# EFR32_IO.net
KiCad netlist of a schematic drawn in Altium Designer
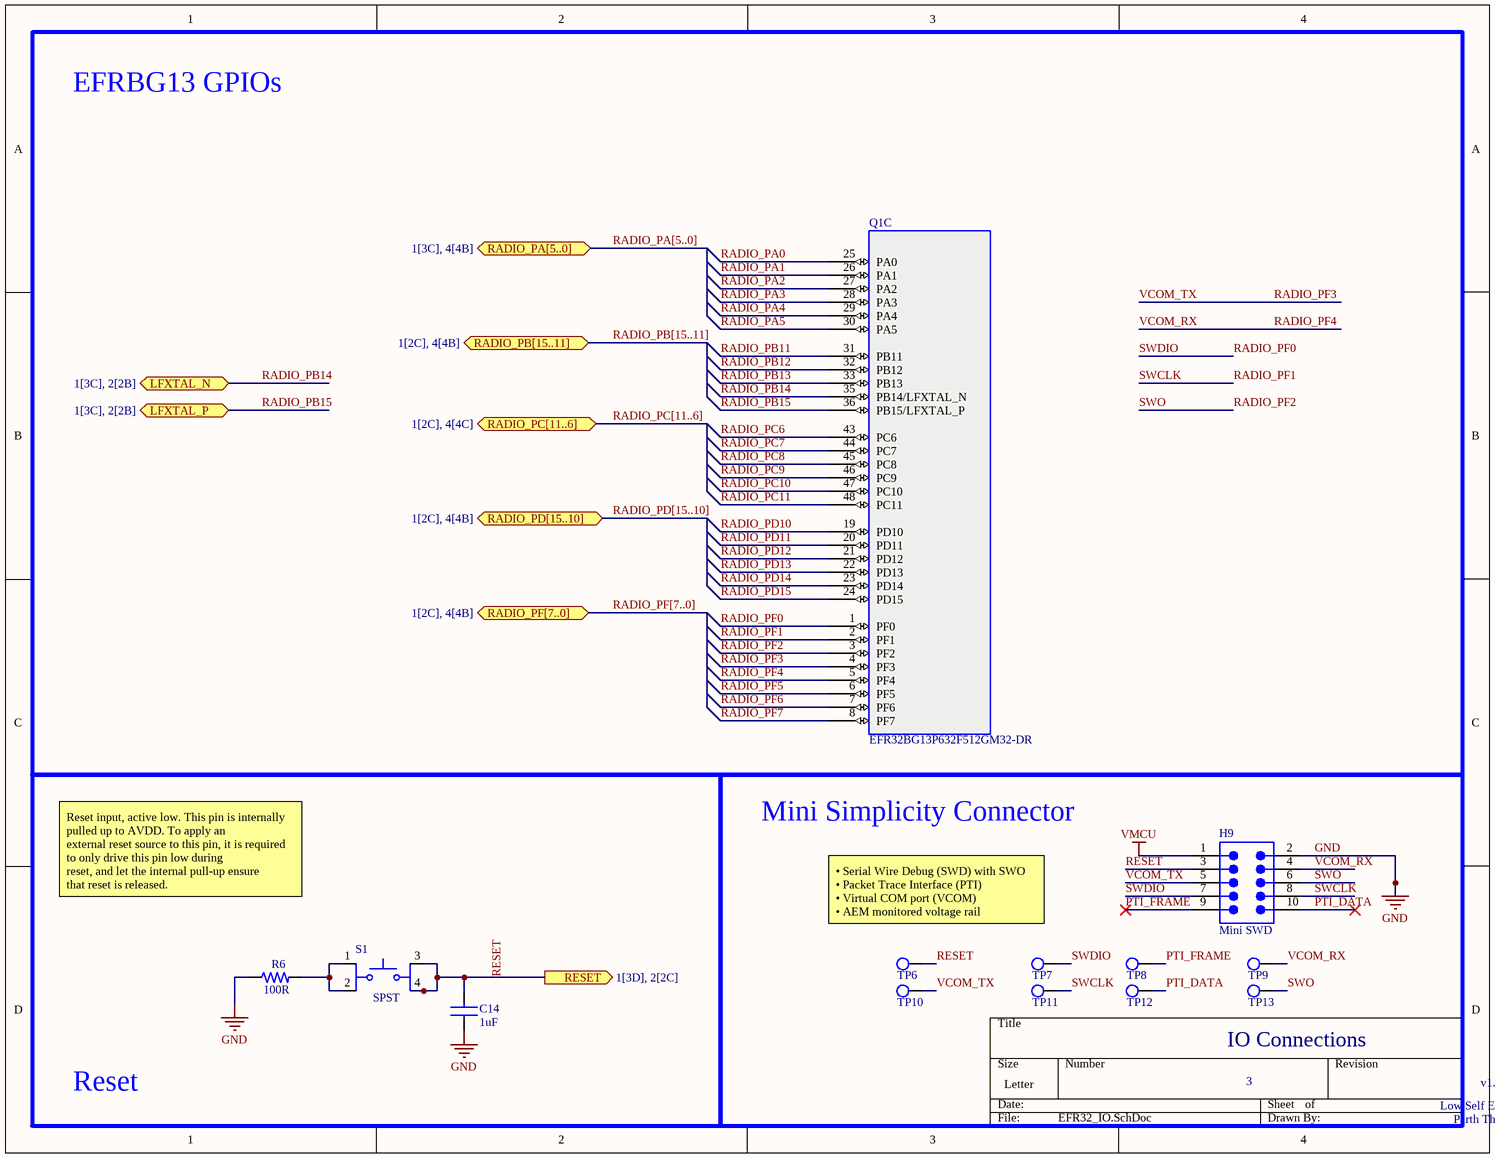
[diagram p0: EFR32_IO.SchDoc]

(export (version "E")
  (design (tool "Eeschema 10.0.6"))
  (components
    (comp (ref "C14")
      (value "1uF")
      (footprint "Capacitor 0603")
      (fields
        (field (name "MANUFACTURER") "Murata")
        (field (name "MANUFACTURER PART NUMBER") "GRM188R61A105KA61D")
        (field (name "Comment") "CAP 1uF 10V 0603")
      )
      (libsource (lib "Keyboard_parts") (part "CAP 1uF 10V 0603"))
    )
    (comp (ref "H9")
      (value "Mini SWD")
      (footprint "Mini Simplicity Connector")
      (description "Mini SWD 0.05\" Pitch Connector - 10 Pin SMT Box Header")
      (fields
        (field (name "MANUFACTURER") "Adafruit Industries")
        (field (name "MANUFACTURER PART NUMBER") "4048")
      )
      (libsource (lib "Keyboard_parts") (part "Debug Connector Mini SWD - 0.05{dblquote}"))
    )
    (comp (ref "Q1")
      (value "EFR32BG13P632F512GM32-DR")
      (footprint "EFR32BG")
      (description "BLue Gecko")
      (fields (field (name "MANUFACTURER") "Silicon Labs"))
      (libsource (lib "Keyboard_parts") (part "EFR32BG13P632F512GM32-DR"))
    )
    (comp (ref "R6")
      (value "100R")
      (footprint "Resistor 0603")
      (fields
        (field (name "MANUFACTURER") "Yageo")
        (field (name "MANUFACTURER PART NUMBER") "RC0603FR-07100RL")
        (field (name "TOLERANCE") "1%")
      )
      (libsource (lib "Keyboard_parts") (part "RES 100R 0603"))
    )
    (comp (ref "S1")
      (value "SPST")
      (footprint "SPST")
      (fields
        (field (name "MANUFACTURER") "E-Switch")
        (field (name "MANUFACTURER PART NUMBER") "TL3301NF260QG")
      )
      (libsource (lib "Keyboard_parts") (part "SPST"))
    )
    (comp (ref "TP6")
      (value "Test point")
      (footprint "Test Point")
      (libsource (lib "Keyboard_parts") (part "Test point"))
    )
    (comp (ref "TP7")
      (value "Test point")
      (footprint "Test Point")
      (libsource (lib "Keyboard_parts") (part "Test point"))
    )
    (comp (ref "TP8")
      (value "Test point")
      (footprint "Test Point")
      (libsource (lib "Keyboard_parts") (part "Test point"))
    )
    (comp (ref "TP9")
      (value "Test point")
      (footprint "Test Point")
      (libsource (lib "Keyboard_parts") (part "Test point"))
    )
    (comp (ref "TP10")
      (value "Test point")
      (footprint "Test Point")
      (libsource (lib "Keyboard_parts") (part "Test point"))
    )
    (comp (ref "TP11")
      (value "Test point")
      (footprint "Test Point")
      (libsource (lib "Keyboard_parts") (part "Test point"))
    )
    (comp (ref "TP12")
      (value "Test point")
      (footprint "Test Point")
      (libsource (lib "Keyboard_parts") (part "Test point"))
    )
    (comp (ref "TP13")
      (value "Test point")
      (footprint "Test Point")
      (libsource (lib "Keyboard_parts") (part "Test point"))
    )
  )
  (nets
    (net (code "1") (name "/PTI_DATA") (class "Default")
      (node (ref "H9") (pin "10") (pinfunction "10_10") (pintype "passive"))
      (node (ref "TP12") (pin "1") (pinfunction "1_1") (pintype "passive"))
    )
    (net (code "2") (name "/PTI_FRAME") (class "Default")
      (node (ref "H9") (pin "9") (pinfunction "9_9") (pintype "passive"))
      (node (ref "TP8") (pin "1") (pinfunction "1_1") (pintype "passive"))
    )
    (net (code "3") (name "/RADIO_PA0") (class "Default")
      (node (ref "Q1") (pin "25") (pinfunction "PA0_25") (pintype "bidirectional"))
    )
    (net (code "4") (name "/RADIO_PA1") (class "Default")
      (node (ref "Q1") (pin "26") (pinfunction "PA1_26") (pintype "bidirectional"))
    )
    (net (code "5") (name "/RADIO_PA2") (class "Default")
      (node (ref "Q1") (pin "27") (pinfunction "PA2_27") (pintype "bidirectional"))
    )
    (net (code "6") (name "/RADIO_PA3") (class "Default")
      (node (ref "Q1") (pin "28") (pinfunction "PA3_28") (pintype "bidirectional"))
    )
    (net (code "7") (name "/RADIO_PA4") (class "Default")
      (node (ref "Q1") (pin "29") (pinfunction "PA4_29") (pintype "bidirectional"))
    )
    (net (code "8") (name "/RADIO_PA5") (class "Default")
      (node (ref "Q1") (pin "30") (pinfunction "PA5_30") (pintype "bidirectional"))
    )
    (net (code "10") (name "/RADIO_PB11") (class "Default")
      (node (ref "Q1") (pin "31") (pinfunction "PB11_31") (pintype "bidirectional"))
    )
    (net (code "11") (name "/RADIO_PB12") (class "Default")
      (node (ref "Q1") (pin "32") (pinfunction "PB12_32") (pintype "bidirectional"))
    )
    (net (code "12") (name "/RADIO_PB13") (class "Default")
      (node (ref "Q1") (pin "33") (pinfunction "PB13_33") (pintype "bidirectional"))
    )
    (net (code "13") (name "/RADIO_PB14") (class "Default")
      (node (ref "Q1") (pin "35") (pinfunction "PB14/LFXTAL_N_35") (pintype "bidirectional"))
    )
    (net (code "14") (name "/RADIO_PB15") (class "Default")
      (node (ref "Q1") (pin "36") (pinfunction "PB15/LFXTAL_P_36") (pintype "bidirectional"))
    )
    (net (code "16") (name "/RADIO_PC6") (class "Default")
      (node (ref "Q1") (pin "43") (pinfunction "PC6_43") (pintype "bidirectional"))
    )
    (net (code "17") (name "/RADIO_PC7") (class "Default")
      (node (ref "Q1") (pin "44") (pinfunction "PC7_44") (pintype "bidirectional"))
    )
    (net (code "18") (name "/RADIO_PC8") (class "Default")
      (node (ref "Q1") (pin "45") (pinfunction "PC8_45") (pintype "bidirectional"))
    )
    (net (code "19") (name "/RADIO_PC9") (class "Default")
      (node (ref "Q1") (pin "46") (pinfunction "PC9_46") (pintype "bidirectional"))
    )
    (net (code "20") (name "/RADIO_PC10") (class "Default")
      (node (ref "Q1") (pin "47") (pinfunction "PC10_47") (pintype "bidirectional"))
    )
    (net (code "21") (name "/RADIO_PC11") (class "Default")
      (node (ref "Q1") (pin "48") (pinfunction "PC11_48") (pintype "bidirectional"))
    )
    (net (code "23") (name "/RADIO_PD10") (class "Default")
      (node (ref "Q1") (pin "19") (pinfunction "PD10_19") (pintype "bidirectional"))
    )
    (net (code "24") (name "/RADIO_PD11") (class "Default")
      (node (ref "Q1") (pin "20") (pinfunction "PD11_20") (pintype "bidirectional"))
    )
    (net (code "25") (name "/RADIO_PD12") (class "Default")
      (node (ref "Q1") (pin "21") (pinfunction "PD12_21") (pintype "bidirectional"))
    )
    (net (code "26") (name "/RADIO_PD13") (class "Default")
      (node (ref "Q1") (pin "22") (pinfunction "PD13_22") (pintype "bidirectional"))
    )
    (net (code "27") (name "/RADIO_PD14") (class "Default")
      (node (ref "Q1") (pin "23") (pinfunction "PD14_23") (pintype "bidirectional"))
    )
    (net (code "28") (name "/RADIO_PD15") (class "Default")
      (node (ref "Q1") (pin "24") (pinfunction "PD15_24") (pintype "bidirectional"))
    )
    (net (code "30") (name "/RADIO_PF0") (class "Default")
      (node (ref "H9") (pin "7") (pinfunction "7_7") (pintype "passive"))
      (node (ref "Q1") (pin "1") (pinfunction "PF0_1") (pintype "bidirectional"))
      (node (ref "TP7") (pin "1") (pinfunction "1_1") (pintype "passive"))
    )
    (net (code "31") (name "/RADIO_PF1") (class "Default")
      (node (ref "H9") (pin "8") (pinfunction "8_8") (pintype "passive"))
      (node (ref "Q1") (pin "2") (pinfunction "PF1_2") (pintype "bidirectional"))
      (node (ref "TP11") (pin "1") (pinfunction "1_1") (pintype "passive"))
    )
    (net (code "32") (name "/RADIO_PF2") (class "Default")
      (node (ref "H9") (pin "6") (pinfunction "6_6") (pintype "passive"))
      (node (ref "Q1") (pin "3") (pinfunction "PF2_3") (pintype "bidirectional"))
      (node (ref "TP13") (pin "1") (pinfunction "1_1") (pintype "passive"))
    )
    (net (code "33") (name "/RADIO_PF3") (class "Default")
      (node (ref "H9") (pin "5") (pinfunction "5_5") (pintype "passive"))
      (node (ref "Q1") (pin "4") (pinfunction "PF3_4") (pintype "bidirectional"))
      (node (ref "TP10") (pin "1") (pinfunction "1_1") (pintype "passive"))
    )
    (net (code "34") (name "/RADIO_PF4") (class "Default")
      (node (ref "H9") (pin "4") (pinfunction "4_4") (pintype "passive"))
      (node (ref "Q1") (pin "5") (pinfunction "PF4_5") (pintype "bidirectional"))
      (node (ref "TP9") (pin "1") (pinfunction "1_1") (pintype "passive"))
    )
    (net (code "35") (name "/RADIO_PF5") (class "Default")
      (node (ref "Q1") (pin "6") (pinfunction "PF5_6") (pintype "bidirectional"))
    )
    (net (code "36") (name "/RADIO_PF6") (class "Default")
      (node (ref "Q1") (pin "7") (pinfunction "PF6_7") (pintype "bidirectional"))
    )
    (net (code "37") (name "/RADIO_PF7") (class "Default")
      (node (ref "Q1") (pin "8") (pinfunction "PF7_8") (pintype "bidirectional"))
    )
    (net (code "39") (name "/RESET") (class "Default")
      (node (ref "C14") (pin "1") (pinfunction "1_1") (pintype "passive"))
      (node (ref "H9") (pin "3") (pinfunction "3_3") (pintype "passive"))
      (node (ref "S1") (pin "3") (pinfunction "3_3") (pintype "passive"))
      (node (ref "S1") (pin "4") (pinfunction "4_4") (pintype "passive"))
      (node (ref "TP6") (pin "1") (pinfunction "1_1") (pintype "passive"))
    )
    (net (code "40") (name "GND") (class "Default")
      (node (ref "C14") (pin "2") (pinfunction "2_2") (pintype "passive"))
      (node (ref "H9") (pin "2") (pinfunction "2_2") (pintype "passive"))
      (node (ref "R6") (pin "1") (pinfunction "1_1") (pintype "passive"))
    )
    (net (code "41") (name "Net-(R6-Pad2)") (class "Default")
      (node (ref "R6") (pin "2") (pinfunction "2_2") (pintype "passive"))
      (node (ref "S1") (pin "1") (pinfunction "1_1") (pintype "passive"))
      (node (ref "S1") (pin "2") (pinfunction "2_2") (pintype "passive"))
    )
    (net (code "42") (name "VMCU") (class "Default")
      (node (ref "H9") (pin "1") (pinfunction "1_1") (pintype "passive"))
    )
  )
)
